# shoff_NADKONVEER.net
KiCad netlist of a schematic drawn in EAGLE
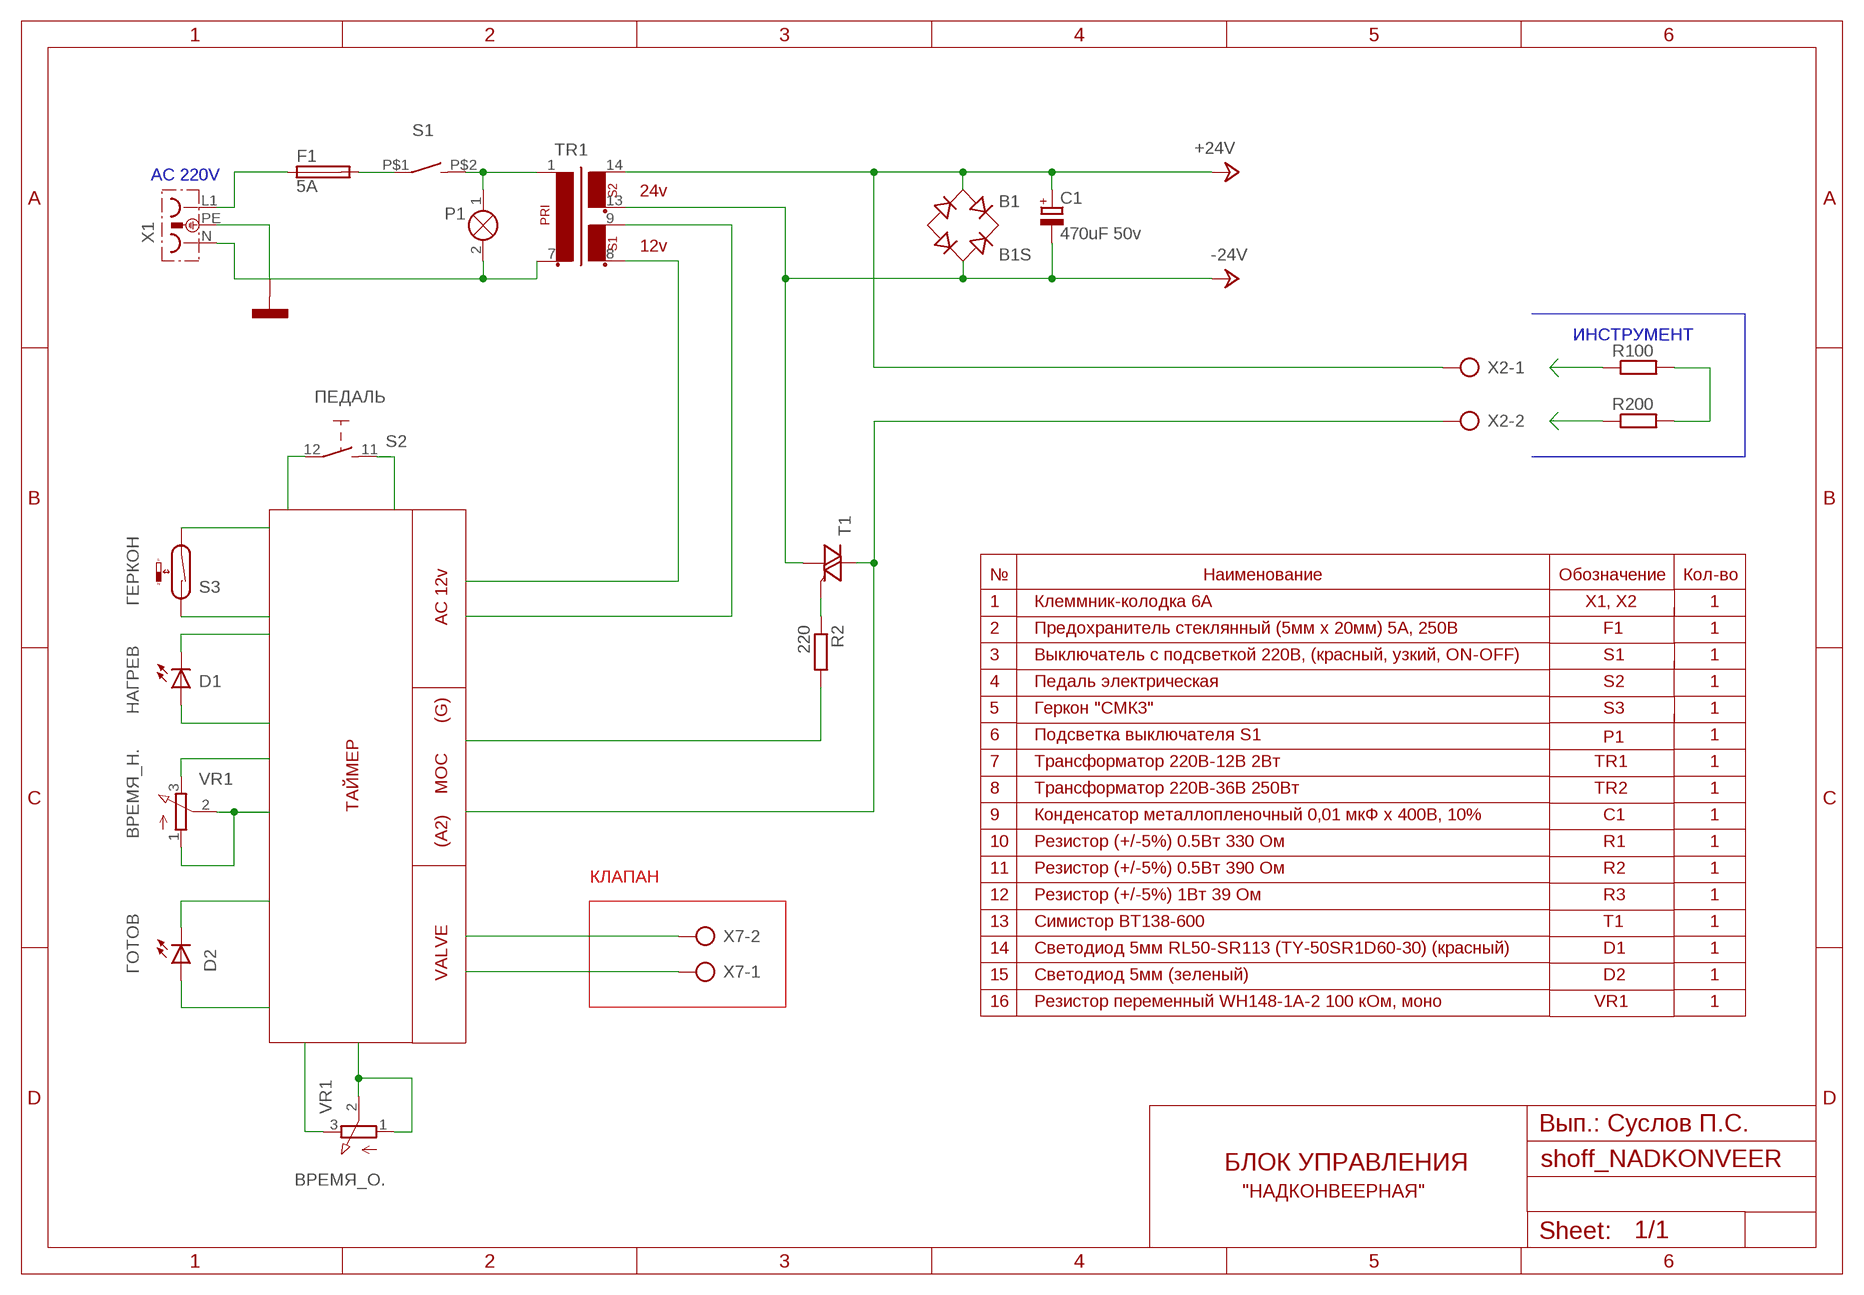
[diagram p0: schematic, sheet 1]

(export (version "E")
  (design (tool "Eeschema 10.0.6"))
  (components
    (comp (ref "B1")
      (value "B1S")
      (footprint "eagle-import:MBS")
      (libsource (lib "eagle-import") (part "BS1"))
    )
    (comp (ref "C1")
      (value "470uF 50v")
      (footprint "eagle-import:085CS_1AW")
      (libsource (lib "eagle-import") (part "CPOL-EU085CS-1AW"))
    )
    (comp (ref "F1")
      (value "5A")
      (footprint "eagle-import:GSH15")
      (fields (field (name "MPN") "64900001039"))
      (libsource (lib "eagle-import") (part "GSH15"))
    )
    (comp (ref "GG")
      (value "MASSE_ALLGEMEIN")
      (footprint "eagle-import:MASSE_ALLGEMEIN")
      (libsource (lib "eagle-import") (part "MASSE_ALLGEMEIN"))
    )
    (comp (ref "P1")
      (value "SIGNALLAMPE")
      (footprint "eagle-import:LAMPE")
      (libsource (lib "eagle-import") (part "SIGNALLAMPE"))
    )
    (comp (ref "R2")
      (value "220")
      (footprint "eagle-import:0207_5V")
      (libsource (lib "eagle-import") (part "R-EU_0207/5V"))
    )
    (comp (ref "R100")
      (value "R-EU_R0201")
      (footprint "eagle-import:R0201")
      (libsource (lib "eagle-import") (part "R-EU_R0201"))
    )
    (comp (ref "R200")
      (value "R-EU_R0201")
      (footprint "eagle-import:R0201")
      (libsource (lib "eagle-import") (part "R-EU_R0201"))
    )
    (comp (ref "S1")
      (value "SCHLIESSER_ARBEITSKONTAKT")
      (footprint "eagle-import:1")
      (libsource (lib "eagle-import") (part "SCHLIESSER_ARBEITSKONTAKT"))
    )
    (comp (ref "S2")
      (value "ПЕДАЛЬ")
      (footprint "eagle-import:KIPPSCHALTER_AUS")
      (libsource (lib "eagle-import") (part "SCHALTER_SCHLIESSER_HANDBETAETIGT"))
    )
    (comp (ref "S3")
      (value "ГЕРКОН")
      (footprint "eagle-import:CT10-G1")
      (fields (field (name "MF") "COTO TECHNOLOGY") (field (name "MPN") "CT10-1530-G1"))
      (libsource (lib "eagle-import") (part "REED-SWITCH-CT10-1530-G1"))
    )
    (comp (ref "T1")
      (value "BTA26-V")
      (footprint "eagle-import:TOP3S-1")
      (libsource (lib "eagle-import") (part "BTA26-V"))
    )
    (comp (ref "TR1")
      (value "EI54-2B")
      (footprint "eagle-import:EI54-2B")
      (libsource (lib "eagle-import") (part "EI54-2B"))
    )
    (comp (ref "X1")
      (value "STECKDOSE")
      (footprint "eagle-import:STECKDOSE")
      (libsource (lib "eagle-import") (part "STECKDOSE"))
    )
    (comp (ref "X2")
      (value "AK500/2")
      (footprint "eagle-import:AK500_2")
      (libsource (lib "eagle-import") (part "AK500/2"))
    )
    (comp (ref "X7")
      (value "AK500/2")
      (footprint "eagle-import:AK500_2")
      (libsource (lib "eagle-import") (part "AK500/2"))
    )
    (comp (ref "ВРЕМЯ_Н.")
      (value "3RP/1610N")
      (footprint "eagle-import:3RP_1610N")
      (libsource (lib "eagle-import") (part "3RP/1610N"))
    )
    (comp (ref "ВРЕМЯ_О.")
      (value "3RP/1610N")
      (footprint "eagle-import:3RP_1610N")
      (libsource (lib "eagle-import") (part "3RP/1610N"))
    )
    (comp (ref "ГОТОВ")
      (value "НАГРЕВ")
      (footprint "eagle-import:LED5MM")
      (libsource (lib "eagle-import") (part "LED5MM"))
    )
    (comp (ref "ГОТОВ1")
      (value "ГОТОВ")
      (footprint "eagle-import:LED5MM")
      (libsource (lib "eagle-import") (part "LED5MM"))
    )
  )
  (nets
    (net (code "1") (name "+24V") (class "Default")
      (node (ref "B1") (pin "AC1") (pinfunction "AC1_AC1") (pintype "passive"))
      (node (ref "C1") (pin "+") (pinfunction "+_+") (pintype "passive"))
      (node (ref "TR1") (pin "14") (pinfunction "6_14") (pintype "passive"))
      (node (ref "X2") (pin "1") (pinfunction "KL_1") (pintype "passive"))
    )
    (net (code "2") (name "-24V") (class "Default")
      (node (ref "B1") (pin "AC2") (pinfunction "AC2_AC2") (pintype "passive"))
      (node (ref "C1") (pin "-") (pinfunction "-_-") (pintype "passive"))
      (node (ref "T1") (pin "A1") (pinfunction "A1_A1") (pintype "passive"))
      (node (ref "TR1") (pin "13") (pinfunction "5_13") (pintype "passive"))
    )
    (net (code "3") (name "Net-(F1-Pad1)") (class "Default")
      (node (ref "F1") (pin "1") (pinfunction "1_1") (pintype "passive"))
      (node (ref "X1") (pin "L1") (pinfunction "L1_L1") (pintype "passive"))
    )
    (net (code "4") (name "Net-(GG-0V)") (class "Default")
      (node (ref "GG") (pin "1") (pinfunction "0V_1") (pintype "passive"))
      (node (ref "X1") (pin "PE") (pinfunction "PE_PE") (pintype "passive"))
    )
    (net (code "5") (name "Net-(P1-X1)") (class "Default")
      (node (ref "P1") (pin "1") (pinfunction "X1_1") (pintype "passive"))
      (node (ref "S1") (pin "P$2") (pinfunction "3_P$2") (pintype "passive"))
      (node (ref "TR1") (pin "1") (pinfunction "1_1") (pintype "passive"))
    )
    (net (code "6") (name "Net-(P1-X2)") (class "Default")
      (node (ref "P1") (pin "2") (pinfunction "X2_2") (pintype "passive"))
      (node (ref "TR1") (pin "7") (pinfunction "2_7") (pintype "passive"))
      (node (ref "X1") (pin "N") (pinfunction "N_N") (pintype "passive"))
    )
    (net (code "7") (name "Net-(R2-Pad1)") (class "Default")
      (node (ref "R2") (pin "1") (pinfunction "1_1") (pintype "passive"))
      (node (ref "T1") (pin "G") (pinfunction "G_G") (pintype "passive"))
    )
    (net (code "8") (name "Net-(R100-Pad2)") (class "Default")
      (node (ref "R100") (pin "2") (pinfunction "2_2") (pintype "passive"))
      (node (ref "R200") (pin "2") (pinfunction "2_2") (pintype "passive"))
    )
    (net (code "9") (name "Net-(S1-4)") (class "Default")
      (node (ref "F1") (pin "2") (pinfunction "2_2") (pintype "passive"))
      (node (ref "S1") (pin "P$1") (pinfunction "4_P$1") (pintype "passive"))
    )
    (net (code "10") (name "Net-(X2B-KL)") (class "Default")
      (node (ref "T1") (pin "A2") (pinfunction "A2_A2") (pintype "passive"))
      (node (ref "X2") (pin "2") (pinfunction "KL_2") (pintype "passive"))
    )
    (net (code "11") (name "Net-(ВРЕМЯ_Н.-A)") (class "Default")
      (node (ref "ВРЕМЯ_Н.") (pin "1") (pinfunction "A_1") (pintype "passive"))
      (node (ref "ВРЕМЯ_Н.") (pin "2") (pinfunction "S_2") (pintype "passive"))
    )
    (net (code "12") (name "Net-(ВРЕМЯ_О.-A)") (class "Default")
      (node (ref "ВРЕМЯ_О.") (pin "1") (pinfunction "A_1") (pintype "passive"))
      (node (ref "ВРЕМЯ_О.") (pin "2") (pinfunction "S_2") (pintype "passive"))
    )
    (net (code "13") (name "unconnected-(B1-Pad+)") (class "Default")
      (node (ref "B1") (pin "+") (pinfunction "+_+") (pintype "passive"))
    )
    (net (code "14") (name "unconnected-(B1-Pad-)") (class "Default")
      (node (ref "B1") (pin "-") (pinfunction "-_-") (pintype "passive"))
    )
    (net (code "15") (name "unconnected-(R2-Pad2)") (class "Default")
      (node (ref "R2") (pin "2") (pinfunction "2_2") (pintype "passive"))
    )
    (net (code "16") (name "unconnected-(R100-Pad1)") (class "Default")
      (node (ref "R100") (pin "1") (pinfunction "1_1") (pintype "passive"))
    )
    (net (code "17") (name "unconnected-(R200-Pad1)") (class "Default")
      (node (ref "R200") (pin "1") (pinfunction "1_1") (pintype "passive"))
    )
    (net (code "18") (name "unconnected-(S2-CS1-Pad11)") (class "Default")
      (node (ref "S2") (pin "11") (pinfunction "CS1_11") (pintype "passive"))
    )
    (net (code "19") (name "unconnected-(S2-S1-Pad12)") (class "Default")
      (node (ref "S2") (pin "12") (pinfunction "S1_12") (pintype "passive"))
    )
    (net (code "20") (name "unconnected-(S3-Pad1)") (class "Default")
      (node (ref "S3") (pin "1") (pinfunction "1_1") (pintype "passive"))
    )
    (net (code "21") (name "unconnected-(S3-Pad2)") (class "Default")
      (node (ref "S3") (pin "2") (pinfunction "2_2") (pintype "passive"))
    )
    (net (code "22") (name "unconnected-(TR1-3-Pad8)") (class "Default")
      (node (ref "TR1") (pin "8") (pinfunction "3_8") (pintype "passive"))
    )
    (net (code "23") (name "unconnected-(TR1-4-Pad9)") (class "Default")
      (node (ref "TR1") (pin "9") (pinfunction "4_9") (pintype "passive"))
    )
    (net (code "24") (name "unconnected-(X7A-KL-Pad1)") (class "Default")
      (node (ref "X7") (pin "1") (pinfunction "KL_1") (pintype "passive"))
    )
    (net (code "25") (name "unconnected-(X7B-KL-Pad2)") (class "Default")
      (node (ref "X7") (pin "2") (pinfunction "KL_2") (pintype "passive"))
    )
    (net (code "26") (name "unconnected-(ВРЕМЯ_Н.-E-Pad3)") (class "Default")
      (node (ref "ВРЕМЯ_Н.") (pin "3") (pinfunction "E_3") (pintype "passive"))
    )
    (net (code "27") (name "unconnected-(ВРЕМЯ_О.-E-Pad3)") (class "Default")
      (node (ref "ВРЕМЯ_О.") (pin "3") (pinfunction "E_3") (pintype "passive"))
    )
    (net (code "28") (name "unconnected-(ГОТОВ-C-PadK)") (class "Default")
      (node (ref "ГОТОВ") (pin "K") (pinfunction "C_K") (pintype "passive"))
    )
    (net (code "29") (name "unconnected-(ГОТОВ-PadA)") (class "Default")
      (node (ref "ГОТОВ") (pin "A") (pinfunction "A_A") (pintype "passive"))
    )
    (net (code "30") (name "unconnected-(ГОТОВ1-C-PadK)") (class "Default")
      (node (ref "ГОТОВ1") (pin "K") (pinfunction "C_K") (pintype "passive"))
    )
    (net (code "31") (name "unconnected-(ГОТОВ1-PadA)") (class "Default")
      (node (ref "ГОТОВ1") (pin "A") (pinfunction "A_A") (pintype "passive"))
    )
  )
)
